# sharpmem_bob.net
KiCad netlist of a schematic drawn in EAGLE
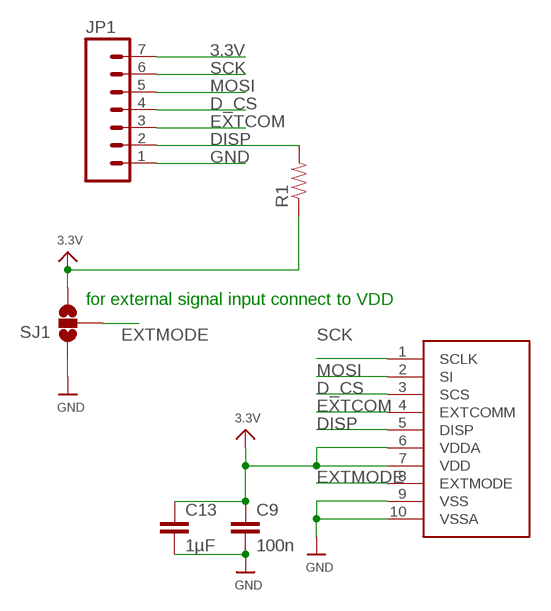
[diagram p0: schematic, sheet 1]

(export (version "E")
  (design (tool "Eeschema 10.0.6"))
  (components
    (comp (ref "C9")
      (value "100n")
      (footprint "eagle-import:C0402")
      (libsource (lib "eagle-import") (part "C-EUC0402"))
    )
    (comp (ref "C13")
      (value "1µF")
      (footprint "eagle-import:C0402")
      (libsource (lib "eagle-import") (part "C-EUC0402"))
    )
    (comp (ref "JP1")
      (value "M07")
      (footprint "eagle-import:1X07")
      (libsource (lib "eagle-import") (part "M07"))
    )
    (comp (ref "R1")
      (value "RESISTOR0402-RES")
      (footprint "eagle-import:0402-RES")
      (libsource (lib "eagle-import") (part "RESISTOR0402-RES"))
    )
    (comp (ref "SJ1")
      (value "SOLDERJUMPER_2WAYS")
      (footprint "eagle-import:SJ_3")
      (libsource (lib "eagle-import") (part "SOLDERJUMPER_2WAYS"))
    )
    (comp (ref "U$2")
      (value "SHARP_MEM_DISP")
      (footprint "eagle-import:Y5BW")
      (libsource (lib "eagle-import") (part "SHARP_MEM_DISP"))
    )
  )
  (nets
    (net (code "1") (name "/DISP") (class "Default")
      (node (ref "JP1") (pin "2") (pinfunction "2_2") (pintype "passive"))
      (node (ref "R1") (pin "2") (pinfunction "2_2") (pintype "passive"))
      (node (ref "U$2") (pin "5") (pinfunction "DISP_5") (pintype "bidirectional"))
    )
    (net (code "2") (name "/D_CS") (class "Default")
      (node (ref "JP1") (pin "4") (pinfunction "4_4") (pintype "passive"))
      (node (ref "U$2") (pin "3") (pinfunction "SCS_3") (pintype "bidirectional"))
    )
    (net (code "3") (name "/EXTCOM") (class "Default")
      (node (ref "JP1") (pin "3") (pinfunction "3_3") (pintype "passive"))
      (node (ref "U$2") (pin "4") (pinfunction "EXTCOMM_4") (pintype "bidirectional"))
    )
    (net (code "4") (name "/EXTMODE") (class "Default")
      (node (ref "SJ1") (pin "2") (pinfunction "2_2") (pintype "passive"))
      (node (ref "U$2") (pin "8") (pinfunction "EXTMODE_8") (pintype "bidirectional"))
    )
    (net (code "5") (name "/MOSI") (class "Default")
      (node (ref "JP1") (pin "5") (pinfunction "5_5") (pintype "passive"))
      (node (ref "U$2") (pin "2") (pinfunction "SI_2") (pintype "bidirectional"))
    )
    (net (code "6") (name "/SCK") (class "Default")
      (node (ref "JP1") (pin "6") (pinfunction "6_6") (pintype "passive"))
      (node (ref "U$2") (pin "1") (pinfunction "SCLK_1") (pintype "bidirectional"))
    )
    (net (code "7") (name "3.3V") (class "Default")
      (node (ref "C13") (pin "1") (pinfunction "1_1") (pintype "passive"))
      (node (ref "C9") (pin "1") (pinfunction "1_1") (pintype "passive"))
      (node (ref "JP1") (pin "7") (pinfunction "7_7") (pintype "passive"))
      (node (ref "R1") (pin "1") (pinfunction "1_1") (pintype "passive"))
      (node (ref "SJ1") (pin "3") (pinfunction "3_3") (pintype "passive"))
      (node (ref "U$2") (pin "6") (pinfunction "VDDA_6") (pintype "bidirectional"))
      (node (ref "U$2") (pin "7") (pinfunction "VDD_7") (pintype "bidirectional"))
    )
    (net (code "8") (name "GND") (class "Default")
      (node (ref "C13") (pin "2") (pinfunction "2_2") (pintype "passive"))
      (node (ref "C9") (pin "2") (pinfunction "2_2") (pintype "passive"))
      (node (ref "JP1") (pin "1") (pinfunction "1_1") (pintype "passive"))
      (node (ref "SJ1") (pin "1") (pinfunction "1_1") (pintype "passive"))
      (node (ref "U$2") (pin "10") (pinfunction "VSSA_10") (pintype "bidirectional"))
      (node (ref "U$2") (pin "9") (pinfunction "VSS_9") (pintype "bidirectional"))
    )
  )
)
